# ELN2_LaboAntenna_Bornet_Cesalli_Lehtinen.net
KiCad netlist of a schematic drawn in Altium Designer
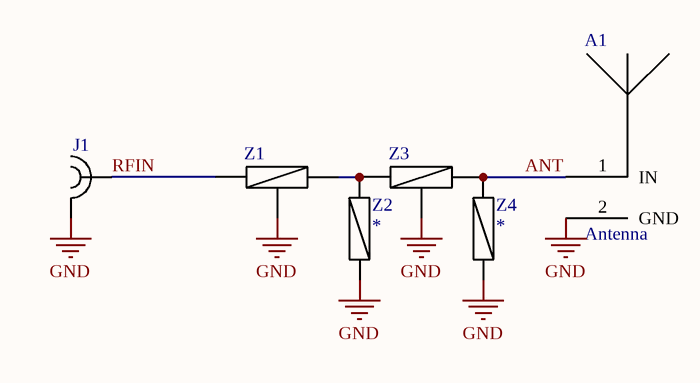
[diagram p0: ELN2_LaboAntenna_Bornet_Cesalli_Lehtinen.SchDoc]

(export (version "E")
  (design (tool "Eeschema 10.0.6"))
  (components
    (comp (ref "A1")
      (value "Antenna")
      (footprint "Antenna")
      (libsource (lib "ELN2_LaboAntenna") (part "Antenna"))
    )
    (comp (ref "J1")
      (value "CONSMA001-G")
      (footprint "SMA EDGE Molex 732511150")
      (description "SMA EDGE Molex 732511150")
      (libsource (lib "Connector") (part "SMA EDGE Molex 732511150"))
    )
    (comp (ref "Z1")
      (value "~")
      (footprint "Matching pad 1005 with Ground")
      (description "Antenna matching pad with ground")
      (libsource (lib "WirelessDevice") (part "Matching pad with ground"))
    )
    (comp (ref "Z2")
      (value "*")
      (footprint "Matching pad 1005")
      (description "Matching pad")
      (libsource (lib "WirelessDevice") (part "Matching pad"))
    )
    (comp (ref "Z3")
      (value "~")
      (footprint "Matching pad 1005 with Ground")
      (description "Antenna matching pad with ground")
      (libsource (lib "WirelessDevice") (part "Matching pad with ground"))
    )
    (comp (ref "Z4")
      (value "*")
      (footprint "Matching pad 1005")
      (description "Matching pad")
      (libsource (lib "WirelessDevice") (part "Matching pad"))
    )
  )
  (nets
    (net (code "1") (name "/ANT") (class "Default")
      (node (ref "A1") (pin "1") (pinfunction "IN_1") (pintype "passive"))
      (node (ref "Z3") (pin "2") (pinfunction "2_2") (pintype "passive"))
      (node (ref "Z4") (pin "2") (pinfunction "2_2") (pintype "passive"))
    )
    (net (code "2") (name "/RFIN") (class "Default")
      (node (ref "J1") (pin "1") (pinfunction "1_1") (pintype "passive"))
      (node (ref "Z1") (pin "1") (pinfunction "1_1") (pintype "passive"))
    )
    (net (code "3") (name "GND") (class "Default")
      (node (ref "A1") (pin "2") (pinfunction "GND_2") (pintype "passive"))
      (node (ref "J1") (pin "2") (pinfunction "2_2") (pintype "passive"))
      (node (ref "Z1") (pin "3") (pinfunction "GND_3") (pintype "passive"))
      (node (ref "Z2") (pin "1") (pinfunction "1_1") (pintype "passive"))
      (node (ref "Z3") (pin "3") (pinfunction "GND_3") (pintype "passive"))
      (node (ref "Z4") (pin "1") (pinfunction "1_1") (pintype "passive"))
    )
    (net (code "4") (name "Net-(Z1-Pad2)") (class "Default")
      (node (ref "Z1") (pin "2") (pinfunction "2_2") (pintype "passive"))
      (node (ref "Z2") (pin "2") (pinfunction "2_2") (pintype "passive"))
      (node (ref "Z3") (pin "1") (pinfunction "1_1") (pintype "passive"))
    )
  )
)
